# ADC.net
KiCad netlist of a schematic drawn in Altium Designer
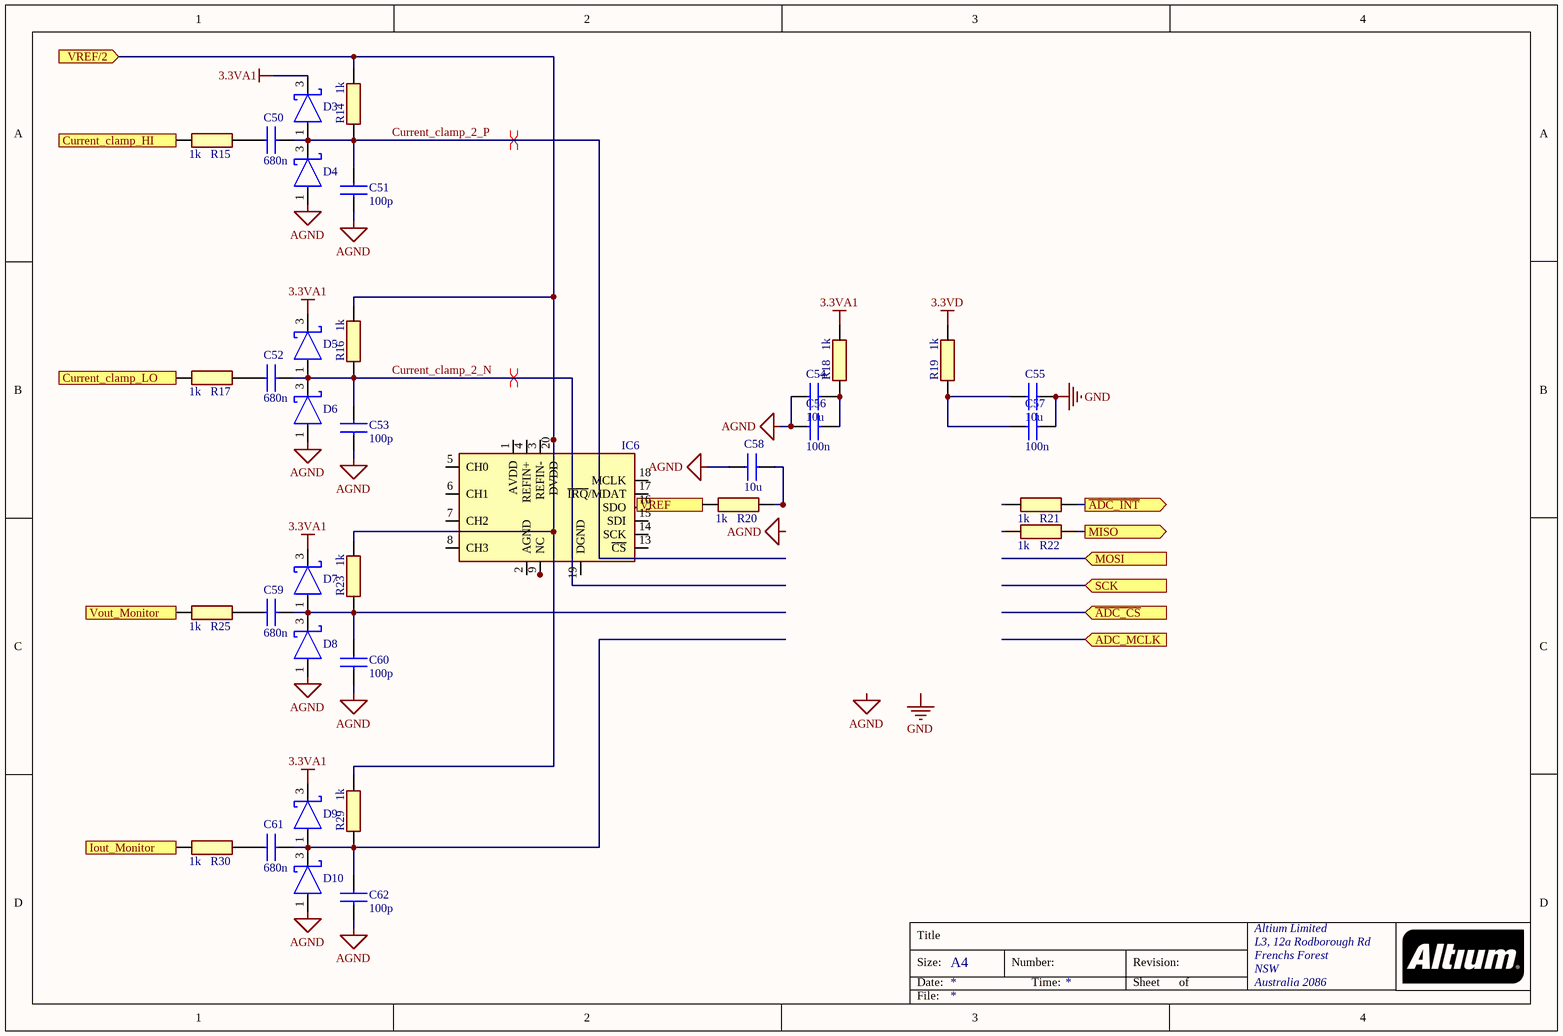
[diagram p0: ADC.SchDoc]

(export (version "E")
  (design (tool "Eeschema 10.0.6"))
  (components
    (comp (ref "C50")
      (value "680n")
      (footprint "PcbLib:R82DC3680AA60J")
      (description "Capacitor")
      (fields
        (field (name "MANUFACTURER_PART_NUMBER") "R82DC3680AA60J")
        (field (name "MOUSER PART NUMBER") "80-R82DC3680AA60J")
      )
      (libsource (lib "Schlib") (part "R82DC3680AA60J"))
    )
    (comp (ref "C51")
      (value "100p")
      (footprint "CAPC2012X140N")
      (description "Capacitor smd ceramic")
      (fields
        (field (name "MANUFACTURER_PART_NUMBER") "C3216C0G1H562J060AA")
        (field (name "Comment") "Capacitor_SMD")
      )
      (libsource (lib "Schlib") (part "Capacitor_SMD"))
    )
    (comp (ref "C52")
      (value "680n")
      (footprint "PcbLib:R82DC3680AA60J")
      (description "Capacitor")
      (fields
        (field (name "MANUFACTURER_PART_NUMBER") "R82DC3680AA60J")
        (field (name "MOUSER PART NUMBER") "80-R82DC3680AA60J")
      )
      (libsource (lib "Schlib") (part "R82DC3680AA60J"))
    )
    (comp (ref "C53")
      (value "100p")
      (footprint "CAPC2012X140N")
      (description "Capacitor smd ceramic")
      (fields
        (field (name "MANUFACTURER_PART_NUMBER") "C3216C0G1H562J060AA")
        (field (name "Comment") "Capacitor_SMD")
      )
      (libsource (lib "Schlib") (part "Capacitor_SMD"))
    )
    (comp (ref "C54")
      (value "10u")
      (footprint "CAPC2012X140N")
      (description "Capacitor smd ceramic")
      (fields
        (field (name "MANUFACTURER_PART_NUMBER") "C3216C0G1H562J060AA")
        (field (name "Comment") "Capacitor_SMD")
      )
      (libsource (lib "Schlib") (part "Capacitor_SMD"))
    )
    (comp (ref "C55")
      (value "10u")
      (footprint "CAPC2012X140N")
      (description "Capacitor smd ceramic")
      (fields
        (field (name "MANUFACTURER_PART_NUMBER") "C3216C0G1H562J060AA")
        (field (name "Comment") "Capacitor_SMD")
      )
      (libsource (lib "Schlib") (part "Capacitor_SMD"))
    )
    (comp (ref "C56")
      (value "100n")
      (footprint "CAPC2012X140N")
      (description "Capacitor smd ceramic")
      (fields
        (field (name "MANUFACTURER_PART_NUMBER") "C3216C0G1H562J060AA")
        (field (name "Comment") "Capacitor_SMD")
      )
      (libsource (lib "Schlib") (part "Capacitor_SMD"))
    )
    (comp (ref "C57")
      (value "100n")
      (footprint "CAPC2012X140N")
      (description "Capacitor smd ceramic")
      (fields
        (field (name "MANUFACTURER_PART_NUMBER") "C3216C0G1H562J060AA")
        (field (name "Comment") "Capacitor_SMD")
      )
      (libsource (lib "Schlib") (part "Capacitor_SMD"))
    )
    (comp (ref "C58")
      (value "10u")
      (footprint "CAPC2012X140N")
      (description "Capacitor smd ceramic")
      (fields
        (field (name "MANUFACTURER_PART_NUMBER") "C3216C0G1H562J060AA")
        (field (name "Comment") "Capacitor_SMD")
      )
      (libsource (lib "Schlib") (part "Capacitor_SMD"))
    )
    (comp (ref "C59")
      (value "680n")
      (footprint "PcbLib:R82DC3680AA60J")
      (description "Capacitor")
      (fields
        (field (name "MANUFACTURER_PART_NUMBER") "R82DC3680AA60J")
        (field (name "MOUSER PART NUMBER") "80-R82DC3680AA60J")
      )
      (libsource (lib "Schlib") (part "R82DC3680AA60J"))
    )
    (comp (ref "C60")
      (value "100p")
      (footprint "CAPC2012X140N")
      (description "Capacitor smd ceramic")
      (fields
        (field (name "MANUFACTURER_PART_NUMBER") "C3216C0G1H562J060AA")
        (field (name "Comment") "Capacitor_SMD")
      )
      (libsource (lib "Schlib") (part "Capacitor_SMD"))
    )
    (comp (ref "C61")
      (value "680n")
      (footprint "PcbLib:R82DC3680AA60J")
      (description "Capacitor")
      (fields
        (field (name "MANUFACTURER_PART_NUMBER") "R82DC3680AA60J")
        (field (name "MOUSER PART NUMBER") "80-R82DC3680AA60J")
      )
      (libsource (lib "Schlib") (part "R82DC3680AA60J"))
    )
    (comp (ref "C62")
      (value "100p")
      (footprint "CAPC2012X140N")
      (description "Capacitor smd ceramic")
      (fields
        (field (name "MANUFACTURER_PART_NUMBER") "C3216C0G1H562J060AA")
        (field (name "Comment") "Capacitor_SMD")
      )
      (libsource (lib "Schlib") (part "Capacitor_SMD"))
    )
    (comp (ref "D3")
      (value "BAS40")
      (footprint "PcbLib:SOT65P210X110-3N")
      (description "Diode")
      (fields
        (field (name "MANUFACTURER_PART_NUMBER") "BAS40-04W,115")
        (field (name "MOUSER PART NUMBER") "771-BAS40-04W-T/R")
      )
      (libsource (lib "Schlib") (part "BAS40"))
    )
    (comp (ref "D4")
      (value "BAS40")
      (footprint "PcbLib:SOT65P210X110-3N")
      (description "Diode")
      (fields
        (field (name "MANUFACTURER_PART_NUMBER") "BAS40-04W,115")
        (field (name "MOUSER PART NUMBER") "771-BAS40-04W-T/R")
      )
      (libsource (lib "Schlib") (part "BAS40"))
    )
    (comp (ref "D5")
      (value "BAS40")
      (footprint "PcbLib:SOT65P210X110-3N")
      (description "Diode")
      (fields
        (field (name "MANUFACTURER_PART_NUMBER") "BAS40-04W,115")
        (field (name "MOUSER PART NUMBER") "771-BAS40-04W-T/R")
      )
      (libsource (lib "Schlib") (part "BAS40"))
    )
    (comp (ref "D6")
      (value "BAS40")
      (footprint "PcbLib:SOT65P210X110-3N")
      (description "Diode")
      (fields
        (field (name "MANUFACTURER_PART_NUMBER") "BAS40-04W,115")
        (field (name "MOUSER PART NUMBER") "771-BAS40-04W-T/R")
      )
      (libsource (lib "Schlib") (part "BAS40"))
    )
    (comp (ref "D7")
      (value "BAS40")
      (footprint "PcbLib:SOT65P210X110-3N")
      (description "Diode")
      (fields
        (field (name "MANUFACTURER_PART_NUMBER") "BAS40-04W,115")
        (field (name "MOUSER PART NUMBER") "771-BAS40-04W-T/R")
      )
      (libsource (lib "Schlib") (part "BAS40"))
    )
    (comp (ref "D8")
      (value "BAS40")
      (footprint "PcbLib:SOT65P210X110-3N")
      (description "Diode")
      (fields
        (field (name "MANUFACTURER_PART_NUMBER") "BAS40-04W,115")
        (field (name "MOUSER PART NUMBER") "771-BAS40-04W-T/R")
      )
      (libsource (lib "Schlib") (part "BAS40"))
    )
    (comp (ref "D9")
      (value "BAS40")
      (footprint "PcbLib:SOT65P210X110-3N")
      (description "Diode")
      (fields
        (field (name "MANUFACTURER_PART_NUMBER") "BAS40-04W,115")
        (field (name "MOUSER PART NUMBER") "771-BAS40-04W-T/R")
      )
      (libsource (lib "Schlib") (part "BAS40"))
    )
    (comp (ref "D10")
      (value "BAS40")
      (footprint "PcbLib:SOT65P210X110-3N")
      (description "Diode")
      (fields
        (field (name "MANUFACTURER_PART_NUMBER") "BAS40-04W,115")
        (field (name "MOUSER PART NUMBER") "771-BAS40-04W-T/R")
      )
      (libsource (lib "Schlib") (part "BAS40"))
    )
    (comp (ref "IC6")
      (value "MCP3462T-E_NC")
      (footprint "SOP65P640X120-20N")
      (description "Integrated Circuit")
      (fields
        (field (name "MANUFACTURER_PART_NUMBER") "MCP3462T-E/NC")
        (field (name "MOUSER PART NUMBER") "579-MCP3462T-E/NC")
      )
      (libsource (lib "SCHLIB2") (part "MCP3462T-E_NC"))
    )
    (comp (ref "R14")
      (value "1k")
      (footprint "RESC2012X60N")
      (description "Resistor SMD")
      (fields
        (field (name "MANUFACTURER_PART_NUMBER") "CR1206-FW-1504ELF")
        (field (name "MOUSER PART NUMBER") "652-CR1206FW1504ELF")
      )
      (libsource (lib "") (part "Res_SMD_1"))
    )
    (comp (ref "R15")
      (value "1k")
      (footprint "RESC2012X60N")
      (description "Resistor SMD")
      (fields
        (field (name "MANUFACTURER_PART_NUMBER") "CR1206-FW-1504ELF")
        (field (name "MOUSER PART NUMBER") "652-CR1206FW1504ELF")
      )
      (libsource (lib "Schlib") (part "Res_SMD"))
    )
    (comp (ref "R16")
      (value "1k")
      (footprint "RESC2012X60N")
      (description "Resistor SMD")
      (fields
        (field (name "MANUFACTURER_PART_NUMBER") "CR1206-FW-1504ELF")
        (field (name "MOUSER PART NUMBER") "652-CR1206FW1504ELF")
      )
      (libsource (lib "") (part "Res_SMD_1"))
    )
    (comp (ref "R17")
      (value "1k")
      (footprint "RESC2012X60N")
      (description "Resistor SMD")
      (fields
        (field (name "MANUFACTURER_PART_NUMBER") "CR1206-FW-1504ELF")
        (field (name "MOUSER PART NUMBER") "652-CR1206FW1504ELF")
      )
      (libsource (lib "Schlib") (part "Res_SMD"))
    )
    (comp (ref "R18")
      (value "1k")
      (footprint "RESC2012X60N")
      (description "Resistor SMD")
      (fields
        (field (name "MANUFACTURER_PART_NUMBER") "CR1206-FW-1504ELF")
        (field (name "MOUSER PART NUMBER") "652-CR1206FW1504ELF")
      )
      (libsource (lib "") (part "Res_SMD_1"))
    )
    (comp (ref "R19")
      (value "1k")
      (footprint "RESC2012X60N")
      (description "Resistor SMD")
      (fields
        (field (name "MANUFACTURER_PART_NUMBER") "CR1206-FW-1504ELF")
        (field (name "MOUSER PART NUMBER") "652-CR1206FW1504ELF")
      )
      (libsource (lib "") (part "Res_SMD_1"))
    )
    (comp (ref "R20")
      (value "1k")
      (footprint "RESC2012X60N")
      (description "Resistor SMD")
      (fields
        (field (name "MANUFACTURER_PART_NUMBER") "CR1206-FW-1504ELF")
        (field (name "MOUSER PART NUMBER") "652-CR1206FW1504ELF")
      )
      (libsource (lib "Schlib") (part "Res_SMD"))
    )
    (comp (ref "R21")
      (value "1k")
      (footprint "RESC2012X60N")
      (description "Resistor SMD")
      (fields
        (field (name "MANUFACTURER_PART_NUMBER") "CR1206-FW-1504ELF")
        (field (name "MOUSER PART NUMBER") "652-CR1206FW1504ELF")
      )
      (libsource (lib "Schlib") (part "Res_SMD"))
    )
    (comp (ref "R22")
      (value "1k")
      (footprint "RESC2012X60N")
      (description "Resistor SMD")
      (fields
        (field (name "MANUFACTURER_PART_NUMBER") "CR1206-FW-1504ELF")
        (field (name "MOUSER PART NUMBER") "652-CR1206FW1504ELF")
      )
      (libsource (lib "Schlib") (part "Res_SMD"))
    )
    (comp (ref "R23")
      (value "1k")
      (footprint "RESC2012X60N")
      (description "Resistor SMD")
      (fields
        (field (name "MANUFACTURER_PART_NUMBER") "CR1206-FW-1504ELF")
        (field (name "MOUSER PART NUMBER") "652-CR1206FW1504ELF")
      )
      (libsource (lib "") (part "Res_SMD_1"))
    )
    (comp (ref "R25")
      (value "1k")
      (footprint "RESC2012X60N")
      (description "Resistor SMD")
      (fields
        (field (name "MANUFACTURER_PART_NUMBER") "CR1206-FW-1504ELF")
        (field (name "MOUSER PART NUMBER") "652-CR1206FW1504ELF")
      )
      (libsource (lib "Schlib") (part "Res_SMD"))
    )
    (comp (ref "R29")
      (value "1k")
      (footprint "RESC2012X60N")
      (description "Resistor SMD")
      (fields
        (field (name "MANUFACTURER_PART_NUMBER") "CR1206-FW-1504ELF")
        (field (name "MOUSER PART NUMBER") "652-CR1206FW1504ELF")
      )
      (libsource (lib "") (part "Res_SMD_1"))
    )
    (comp (ref "R30")
      (value "1k")
      (footprint "RESC2012X60N")
      (description "Resistor SMD")
      (fields
        (field (name "MANUFACTURER_PART_NUMBER") "CR1206-FW-1504ELF")
        (field (name "MOUSER PART NUMBER") "652-CR1206FW1504ELF")
      )
      (libsource (lib "Schlib") (part "Res_SMD"))
    )
  )
  (nets
    (net (code "2") (name "/ADC_INT") (class "Default")
      (node (ref "R21") (pin "1") (pinfunction "1_1") (pintype "passive"))
    )
    (net (code "4") (name "/Current_clamp_2_N") (class "Default")
      (node (ref "C52") (pin "2") (pinfunction "2_2") (pintype "passive"))
      (node (ref "C53") (pin "1") (pinfunction "1_1") (pintype "passive"))
      (node (ref "D5") (pin "1") (pinfunction "A_1") (pintype "passive"))
      (node (ref "D6") (pin "3") (pinfunction "K_3") (pintype "passive"))
      (node (ref "R16") (pin "1") (pinfunction "1_1") (pintype "passive"))
    )
    (net (code "5") (name "/Current_clamp_2_P") (class "Default")
      (node (ref "C50") (pin "2") (pinfunction "2_2") (pintype "passive"))
      (node (ref "C51") (pin "1") (pinfunction "1_1") (pintype "passive"))
      (node (ref "D3") (pin "1") (pinfunction "A_1") (pintype "passive"))
      (node (ref "D4") (pin "3") (pinfunction "K_3") (pintype "passive"))
      (node (ref "R14") (pin "1") (pinfunction "1_1") (pintype "passive"))
    )
    (net (code "6") (name "/Current_clamp_HI") (class "Default")
      (node (ref "R15") (pin "2") (pinfunction "2_2") (pintype "passive"))
    )
    (net (code "7") (name "/Current_clamp_LO") (class "Default")
      (node (ref "R17") (pin "2") (pinfunction "2_2") (pintype "passive"))
    )
    (net (code "8") (name "/Iout_Monitor") (class "Default")
      (node (ref "R30") (pin "2") (pinfunction "2_2") (pintype "passive"))
    )
    (net (code "9") (name "/MISO") (class "Default")
      (node (ref "R22") (pin "1") (pinfunction "1_1") (pintype "passive"))
    )
    (net (code "12") (name "/VREF") (class "Default")
      (node (ref "R20") (pin "2") (pinfunction "2_2") (pintype "passive"))
    )
    (net (code "13") (name "/VREF{slash}2") (class "Default")
      (node (ref "IC6") (pin "20") (pinfunction "DVDD_20") (pintype "passive"))
      (node (ref "R14") (pin "2") (pinfunction "2_2") (pintype "passive"))
      (node (ref "R16") (pin "2") (pinfunction "2_2") (pintype "passive"))
      (node (ref "R23") (pin "2") (pinfunction "2_2") (pintype "passive"))
      (node (ref "R29") (pin "2") (pinfunction "2_2") (pintype "passive"))
    )
    (net (code "14") (name "/Vout_Monitor") (class "Default")
      (node (ref "R25") (pin "2") (pinfunction "2_2") (pintype "passive"))
    )
    (net (code "15") (name "3.3VA1") (class "Default")
      (node (ref "D3") (pin "3") (pinfunction "K_3") (pintype "passive"))
      (node (ref "D5") (pin "3") (pinfunction "K_3") (pintype "passive"))
      (node (ref "D7") (pin "3") (pinfunction "K_3") (pintype "passive"))
      (node (ref "D9") (pin "3") (pinfunction "K_3") (pintype "passive"))
      (node (ref "R18") (pin "2") (pinfunction "2_2") (pintype "passive"))
    )
    (net (code "16") (name "3.3VD") (class "Default")
      (node (ref "R19") (pin "2") (pinfunction "2_2") (pintype "passive"))
    )
    (net (code "17") (name "AGND") (class "Default")
      (node (ref "C51") (pin "2") (pinfunction "2_2") (pintype "passive"))
      (node (ref "C53") (pin "2") (pinfunction "2_2") (pintype "passive"))
      (node (ref "C54") (pin "2") (pinfunction "2_2") (pintype "passive"))
      (node (ref "C56") (pin "2") (pinfunction "2_2") (pintype "passive"))
      (node (ref "C58") (pin "2") (pinfunction "2_2") (pintype "passive"))
      (node (ref "C60") (pin "2") (pinfunction "2_2") (pintype "passive"))
      (node (ref "C62") (pin "2") (pinfunction "2_2") (pintype "passive"))
      (node (ref "D10") (pin "1") (pinfunction "A_1") (pintype "passive"))
      (node (ref "D4") (pin "1") (pinfunction "A_1") (pintype "passive"))
      (node (ref "D6") (pin "1") (pinfunction "A_1") (pintype "passive"))
      (node (ref "D8") (pin "1") (pinfunction "A_1") (pintype "passive"))
    )
    (net (code "18") (name "GND") (class "Default")
      (node (ref "C55") (pin "1") (pinfunction "1_1") (pintype "passive"))
      (node (ref "C57") (pin "1") (pinfunction "1_1") (pintype "passive"))
    )
    (net (code "19") (name "Net-(C50-Pad1)") (class "Default")
      (node (ref "C50") (pin "1") (pinfunction "1_1") (pintype "passive"))
      (node (ref "R15") (pin "1") (pinfunction "1_1") (pintype "passive"))
    )
    (net (code "20") (name "Net-(C52-Pad1)") (class "Default")
      (node (ref "C52") (pin "1") (pinfunction "1_1") (pintype "passive"))
      (node (ref "R17") (pin "1") (pinfunction "1_1") (pintype "passive"))
    )
    (net (code "21") (name "Net-(C54-Pad1)") (class "Default")
      (node (ref "C54") (pin "1") (pinfunction "1_1") (pintype "passive"))
      (node (ref "C56") (pin "1") (pinfunction "1_1") (pintype "passive"))
      (node (ref "R18") (pin "1") (pinfunction "1_1") (pintype "passive"))
    )
    (net (code "22") (name "Net-(C55-Pad2)") (class "Default")
      (node (ref "C55") (pin "2") (pinfunction "2_2") (pintype "passive"))
      (node (ref "C57") (pin "2") (pinfunction "2_2") (pintype "passive"))
      (node (ref "R19") (pin "1") (pinfunction "1_1") (pintype "passive"))
    )
    (net (code "23") (name "Net-(C58-Pad1)") (class "Default")
      (node (ref "C58") (pin "1") (pinfunction "1_1") (pintype "passive"))
      (node (ref "R20") (pin "1") (pinfunction "1_1") (pintype "passive"))
    )
    (net (code "24") (name "Net-(C59-Pad1)") (class "Default")
      (node (ref "C59") (pin "1") (pinfunction "1_1") (pintype "passive"))
      (node (ref "R25") (pin "1") (pinfunction "1_1") (pintype "passive"))
    )
    (net (code "25") (name "Net-(C61-Pad1)") (class "Default")
      (node (ref "C61") (pin "1") (pinfunction "1_1") (pintype "passive"))
      (node (ref "R30") (pin "1") (pinfunction "1_1") (pintype "passive"))
    )
    (net (code "26") (name "Net-(D7-A)") (class "Default")
      (node (ref "C59") (pin "2") (pinfunction "2_2") (pintype "passive"))
      (node (ref "C60") (pin "1") (pinfunction "1_1") (pintype "passive"))
      (node (ref "D7") (pin "1") (pinfunction "A_1") (pintype "passive"))
      (node (ref "D8") (pin "3") (pinfunction "K_3") (pintype "passive"))
      (node (ref "R23") (pin "1") (pinfunction "1_1") (pintype "passive"))
    )
    (net (code "27") (name "Net-(D10-K)") (class "Default")
      (node (ref "C61") (pin "2") (pinfunction "2_2") (pintype "passive"))
      (node (ref "C62") (pin "1") (pinfunction "1_1") (pintype "passive"))
      (node (ref "D10") (pin "3") (pinfunction "K_3") (pintype "passive"))
      (node (ref "D9") (pin "1") (pinfunction "A_1") (pintype "passive"))
      (node (ref "R29") (pin "1") (pinfunction "1_1") (pintype "passive"))
    )
    (net (code "28") (name "Net-(IC6-NC-Pad10)") (class "Default")
      (node (ref "IC6") (pin "10") (pinfunction "NC_10") (pintype "passive"))
      (node (ref "IC6") (pin "11") (pinfunction "NC_11") (pintype "passive"))
      (node (ref "IC6") (pin "12") (pinfunction "NC_12") (pintype "passive"))
      (node (ref "IC6") (pin "9") (pinfunction "NC_9") (pintype "passive"))
    )
    (net (code "29") (name "unconnected-(IC6-AGND-Pad2)") (class "Default")
      (node (ref "IC6") (pin "2") (pinfunction "AGND_2") (pintype "passive"))
    )
    (net (code "30") (name "unconnected-(IC6-AVDD-Pad1)") (class "Default")
      (node (ref "IC6") (pin "1") (pinfunction "AVDD_1") (pintype "passive"))
    )
    (net (code "31") (name "unconnected-(IC6-CH0-Pad5)") (class "Default")
      (node (ref "IC6") (pin "5") (pinfunction "CH0_5") (pintype "passive"))
    )
    (net (code "32") (name "unconnected-(IC6-CH1-Pad6)") (class "Default")
      (node (ref "IC6") (pin "6") (pinfunction "CH1_6") (pintype "passive"))
    )
    (net (code "33") (name "unconnected-(IC6-CH2-Pad7)") (class "Default")
      (node (ref "IC6") (pin "7") (pinfunction "CH2_7") (pintype "passive"))
    )
    (net (code "34") (name "unconnected-(IC6-CH3-Pad8)") (class "Default")
      (node (ref "IC6") (pin "8") (pinfunction "CH3_8") (pintype "passive"))
    )
    (net (code "35") (name "unconnected-(IC6-DGND-Pad19)") (class "Default")
      (node (ref "IC6") (pin "19") (pinfunction "DGND_19") (pintype "passive"))
    )
    (net (code "36") (name "unconnected-(IC6-MCLK-Pad18)") (class "Default")
      (node (ref "IC6") (pin "18") (pinfunction "MCLK_18") (pintype "passive"))
    )
    (net (code "37") (name "unconnected-(IC6-REFIN+-Pad4)") (class "Default")
      (node (ref "IC6") (pin "4") (pinfunction "REFIN+_4") (pintype "passive"))
    )
    (net (code "38") (name "unconnected-(IC6-REFIN--Pad3)") (class "Default")
      (node (ref "IC6") (pin "3") (pinfunction "REFIN-_3") (pintype "passive"))
    )
    (net (code "39") (name "unconnected-(IC6-SCK-Pad14)") (class "Default")
      (node (ref "IC6") (pin "14") (pinfunction "SCK_14") (pintype "passive"))
    )
    (net (code "40") (name "unconnected-(IC6-SDI-Pad15)") (class "Default")
      (node (ref "IC6") (pin "15") (pinfunction "SDI_15") (pintype "passive"))
    )
    (net (code "41") (name "unconnected-(IC6-SDO-Pad16)") (class "Default")
      (node (ref "IC6") (pin "16") (pinfunction "SDO_16") (pintype "passive"))
    )
    (net (code "42") (name "unconnected-(IC6-~{CS}-Pad13)") (class "Default")
      (node (ref "IC6") (pin "13") (pinfunction "~{CS}_13") (pintype "passive"))
    )
    (net (code "43") (name "unconnected-(IC6-~{IRQ}{slash}MDAT-Pad17)") (class "Default")
      (node (ref "IC6") (pin "17") (pinfunction "~{IRQ}/MDAT_17") (pintype "passive"))
    )
    (net (code "44") (name "unconnected-(R21-Pad2)") (class "Default")
      (node (ref "R21") (pin "2") (pinfunction "2_2") (pintype "passive"))
    )
    (net (code "45") (name "unconnected-(R22-Pad2)") (class "Default")
      (node (ref "R22") (pin "2") (pinfunction "2_2") (pintype "passive"))
    )
  )
)
